# ECU_Sheet3.net
KiCad netlist of a schematic drawn in Altium Designer
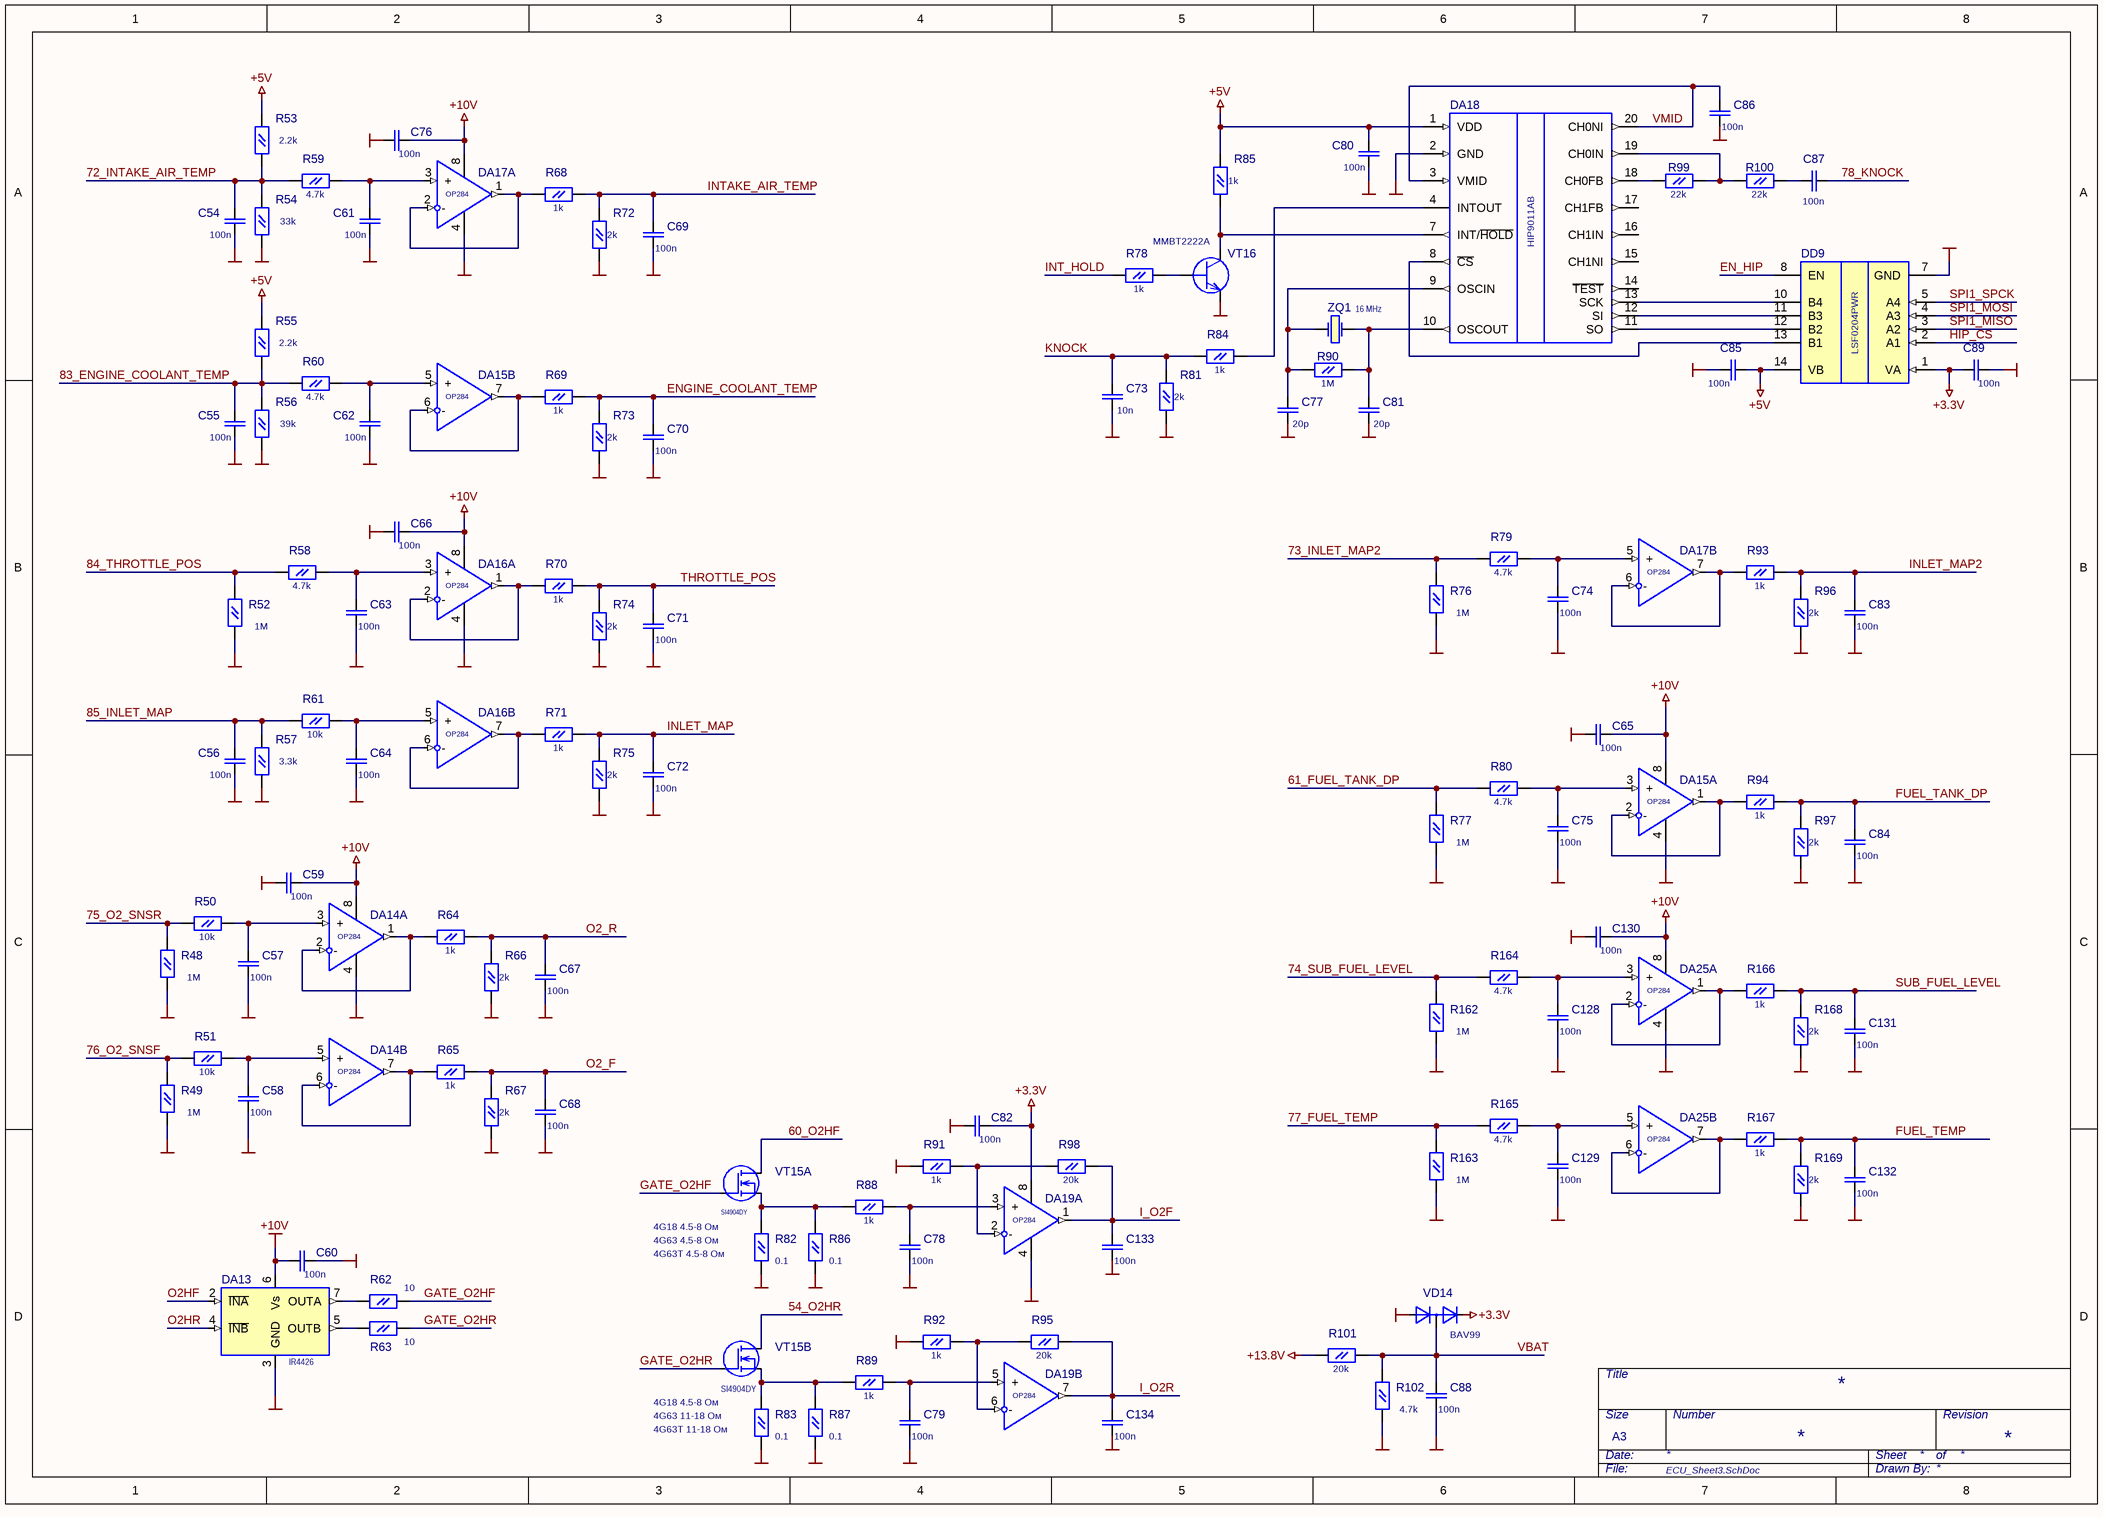
[diagram p0: ECU_Sheet3.SchDoc]

(export (version "E")
  (design (tool "Eeschema 10.0.6"))
  (components
    (comp (ref "C54")
      (value "100n")
      (footprint "C0805L")
      (description "C0603")
      (fields (field (name "Comment") "CSMD"))
      (libsource (lib "L1") (part "CSMD"))
    )
    (comp (ref "C55")
      (value "100n")
      (footprint "C0805L")
      (description "C0603")
      (fields (field (name "Comment") "CSMD"))
      (libsource (lib "L1") (part "CSMD"))
    )
    (comp (ref "C56")
      (value "100n")
      (footprint "C0805L")
      (description "C0603")
      (fields (field (name "Comment") "CSMD"))
      (libsource (lib "L1") (part "CSMD"))
    )
    (comp (ref "C57")
      (value "100n")
      (footprint "C0805L")
      (description "C0603")
      (fields (field (name "Comment") "CSMD"))
      (libsource (lib "L1") (part "CSMD"))
    )
    (comp (ref "C58")
      (value "100n")
      (footprint "C0805L")
      (description "C0603")
      (fields (field (name "Comment") "CSMD"))
      (libsource (lib "L1") (part "CSMD"))
    )
    (comp (ref "C59")
      (value "100n")
      (footprint "C0805L")
      (description "C0603")
      (fields (field (name "Comment") "CSMD"))
      (libsource (lib "L1") (part "CSMD"))
    )
    (comp (ref "C60")
      (value "100n")
      (footprint "C0805L")
      (description "C0603")
      (fields (field (name "Comment") "CSMD"))
      (libsource (lib "L1") (part "CSMD"))
    )
    (comp (ref "C61")
      (value "100n")
      (footprint "C0805L")
      (description "C0603")
      (fields (field (name "Comment") "CSMD"))
      (libsource (lib "L1") (part "CSMD"))
    )
    (comp (ref "C62")
      (value "100n")
      (footprint "C0805L")
      (description "C0603")
      (fields (field (name "Comment") "CSMD"))
      (libsource (lib "L1") (part "CSMD"))
    )
    (comp (ref "C63")
      (value "100n")
      (footprint "C0805L")
      (description "C0603")
      (fields (field (name "Comment") "CSMD"))
      (libsource (lib "L1") (part "CSMD"))
    )
    (comp (ref "C64")
      (value "100n")
      (footprint "C0805L")
      (description "C0603")
      (fields (field (name "Comment") "CSMD"))
      (libsource (lib "L1") (part "CSMD"))
    )
    (comp (ref "C65")
      (value "100n")
      (footprint "C0805L")
      (description "C0603")
      (fields (field (name "Comment") "CSMD"))
      (libsource (lib "L1") (part "CSMD"))
    )
    (comp (ref "C66")
      (value "100n")
      (footprint "C0805L")
      (description "C0603")
      (fields (field (name "Comment") "CSMD"))
      (libsource (lib "L1") (part "CSMD"))
    )
    (comp (ref "C67")
      (value "100n")
      (footprint "C0603L")
      (description "C0603")
      (fields (field (name "Comment") "CSMD"))
      (libsource (lib "L1") (part "CSMD"))
    )
    (comp (ref "C68")
      (value "100n")
      (footprint "C0603L")
      (description "C0603")
      (fields (field (name "Comment") "CSMD"))
      (libsource (lib "L1") (part "CSMD"))
    )
    (comp (ref "C69")
      (value "100n")
      (footprint "C0603L")
      (description "C0603")
      (fields (field (name "Comment") "CSMD"))
      (libsource (lib "L1") (part "CSMD"))
    )
    (comp (ref "C70")
      (value "100n")
      (footprint "C0603L")
      (description "C0603")
      (fields (field (name "Comment") "CSMD"))
      (libsource (lib "L1") (part "CSMD"))
    )
    (comp (ref "C71")
      (value "100n")
      (footprint "C0603L")
      (description "C0603")
      (fields (field (name "Comment") "CSMD"))
      (libsource (lib "L1") (part "CSMD"))
    )
    (comp (ref "C72")
      (value "100n")
      (footprint "C0603L")
      (description "C0603")
      (fields (field (name "Comment") "CSMD"))
      (libsource (lib "L1") (part "CSMD"))
    )
    (comp (ref "C73")
      (value "10n")
      (footprint "C0603L")
      (description "C0603")
      (fields (field (name "Comment") "CSMD"))
      (libsource (lib "L1") (part "CSMD"))
    )
    (comp (ref "C74")
      (value "100n")
      (footprint "C0805L")
      (description "C0603")
      (fields (field (name "Comment") "CSMD"))
      (libsource (lib "L1") (part "CSMD"))
    )
    (comp (ref "C75")
      (value "100n")
      (footprint "C0805L")
      (description "C0603")
      (fields (field (name "Comment") "CSMD"))
      (libsource (lib "L1") (part "CSMD"))
    )
    (comp (ref "C76")
      (value "100n")
      (footprint "C0805L")
      (description "C0603")
      (fields (field (name "Comment") "CSMD"))
      (libsource (lib "L1") (part "CSMD"))
    )
    (comp (ref "C77")
      (value "20p")
      (footprint "C0805L")
      (description "C0603")
      (fields (field (name "Comment") "CSMD"))
      (libsource (lib "L1") (part "CSMD"))
    )
    (comp (ref "C78")
      (value "100n")
      (footprint "C0805L")
      (description "C0603")
      (fields (field (name "Comment") "CSMD"))
      (libsource (lib "L1") (part "CSMD"))
    )
    (comp (ref "C79")
      (value "100n")
      (footprint "C0805L")
      (description "C0603")
      (fields (field (name "Comment") "CSMD"))
      (libsource (lib "L1") (part "CSMD"))
    )
    (comp (ref "C80")
      (value "100n")
      (footprint "C0805L")
      (description "C0603")
      (fields (field (name "Comment") "CSMD"))
      (libsource (lib "") (part "CSMD_1"))
    )
    (comp (ref "C81")
      (value "20p")
      (footprint "C0805L")
      (description "C0603")
      (fields (field (name "Comment") "CSMD"))
      (libsource (lib "L1") (part "CSMD"))
    )
    (comp (ref "C82")
      (value "100n")
      (footprint "C0805L")
      (description "C0603")
      (fields (field (name "Comment") "CSMD"))
      (libsource (lib "L1") (part "CSMD"))
    )
    (comp (ref "C83")
      (value "100n")
      (footprint "C0603L")
      (description "C0603")
      (fields (field (name "Comment") "CSMD"))
      (libsource (lib "L1") (part "CSMD"))
    )
    (comp (ref "C84")
      (value "100n")
      (footprint "C0603L")
      (description "C0603")
      (fields (field (name "Comment") "CSMD"))
      (libsource (lib "L1") (part "CSMD"))
    )
    (comp (ref "C85")
      (value "100n")
      (footprint "C0805L")
      (description "C0603")
      (fields (field (name "Comment") "CSMD"))
      (libsource (lib "L1") (part "CSMD"))
    )
    (comp (ref "C86")
      (value "100n")
      (footprint "C0805L")
      (description "C0603")
      (fields (field (name "Comment") "CSMD"))
      (libsource (lib "L1") (part "CSMD"))
    )
    (comp (ref "C87")
      (value "100n")
      (footprint "C0805L")
      (description "C0603")
      (fields (field (name "Comment") "CSMD"))
      (libsource (lib "L1") (part "CSMD"))
    )
    (comp (ref "C88")
      (value "100n")
      (footprint "C0603L")
      (description "C0603")
      (fields (field (name "Comment") "CSMD"))
      (libsource (lib "L1") (part "CSMD"))
    )
    (comp (ref "C89")
      (value "100n")
      (footprint "C0805L")
      (description "C0603")
      (fields (field (name "Comment") "CSMD"))
      (libsource (lib "L1") (part "CSMD"))
    )
    (comp (ref "C128")
      (value "100n")
      (footprint "C0805L")
      (description "C0603")
      (fields (field (name "Comment") "CSMD"))
      (libsource (lib "L1") (part "CSMD"))
    )
    (comp (ref "C129")
      (value "100n")
      (footprint "C0805L")
      (description "C0603")
      (fields (field (name "Comment") "CSMD"))
      (libsource (lib "L1") (part "CSMD"))
    )
    (comp (ref "C130")
      (value "100n")
      (footprint "C0805L")
      (description "C0603")
      (fields (field (name "Comment") "CSMD"))
      (libsource (lib "L1") (part "CSMD"))
    )
    (comp (ref "C131")
      (value "100n")
      (footprint "C0603L")
      (description "C0603")
      (fields (field (name "Comment") "CSMD"))
      (libsource (lib "L1") (part "CSMD"))
    )
    (comp (ref "C132")
      (value "100n")
      (footprint "C0603L")
      (description "C0603")
      (fields (field (name "Comment") "CSMD"))
      (libsource (lib "L1") (part "CSMD"))
    )
    (comp (ref "C133")
      (value "100n")
      (footprint "C0603L")
      (description "C0603")
      (fields (field (name "Comment") "CSMD"))
      (libsource (lib "L1") (part "CSMD"))
    )
    (comp (ref "C134")
      (value "100n")
      (footprint "C0603L")
      (description "C0603")
      (fields (field (name "Comment") "CSMD"))
      (libsource (lib "L1") (part "CSMD"))
    )
    (comp (ref "DA13") (value "IR4426") (footprint "SOIC8 JEDEC") (libsource (lib "SCH") (part "IR4426")))
    (comp (ref "DA14") (value "OP284") (footprint "SOIC8 JEDEC") (libsource (lib "RL1") (part "AD822")))
    (comp (ref "DA15") (value "OP284") (footprint "SOIC8 JEDEC") (libsource (lib "RL1") (part "AD822")))
    (comp (ref "DA16") (value "OP284") (footprint "SOIC8 JEDEC") (libsource (lib "RL1") (part "AD822")))
    (comp (ref "DA17") (value "OP284") (footprint "SOIC8 JEDEC") (libsource (lib "RL1") (part "AD822")))
    (comp (ref "DA18")
      (value "HIP9011AB")
      (footprint "SOIC-20 (JEDEC MS-013-AC)")
      (libsource (lib "ECULIB") (part "HIP9011AB"))
    )
    (comp (ref "DA19") (value "OP284") (footprint "SOIC8 JEDEC") (libsource (lib "RL1") (part "AD822")))
    (comp (ref "DA25") (value "OP284") (footprint "SOIC8 JEDEC") (libsource (lib "RL1") (part "AD822")))
    (comp (ref "DD9")
      (value "LSF0204PWR")
      (footprint "TSSOP14 (JEDEC MO-153)")
      (libsource (lib "L1") (part "LSF0204PWR"))
    )
    (comp (ref "R48")
      (value "1M")
      (footprint "R0805L")
      (description "R0805")
      (fields (field (name "Comment") "RSMD"))
      (libsource (lib "L1") (part "RSMD"))
    )
    (comp (ref "R49")
      (value "1M")
      (footprint "R0805L")
      (description "R0805")
      (fields (field (name "Comment") "RSMD"))
      (libsource (lib "L1") (part "RSMD"))
    )
    (comp (ref "R50")
      (value "10k")
      (footprint "R0805L")
      (description "R0805")
      (fields (field (name "Comment") "RSMD"))
      (libsource (lib "L1") (part "RSMD"))
    )
    (comp (ref "R51")
      (value "10k")
      (footprint "R0805L")
      (description "R0805")
      (fields (field (name "Comment") "RSMD"))
      (libsource (lib "L1") (part "RSMD"))
    )
    (comp (ref "R52")
      (value "1M")
      (footprint "R0805L")
      (description "R0805")
      (fields (field (name "Comment") "RSMD"))
      (libsource (lib "L1") (part "RSMD"))
    )
    (comp (ref "R53")
      (value "2.2k")
      (footprint "R0805L")
      (description "R0805")
      (fields (field (name "Comment") "RSMD"))
      (libsource (lib "L1") (part "RSMD"))
    )
    (comp (ref "R54")
      (value "33k")
      (footprint "R0805L")
      (description "R0805")
      (fields (field (name "Comment") "RSMD"))
      (libsource (lib "L1") (part "RSMD"))
    )
    (comp (ref "R55")
      (value "2.2k")
      (footprint "R0805L")
      (description "R0805")
      (fields (field (name "Comment") "RSMD"))
      (libsource (lib "L1") (part "RSMD"))
    )
    (comp (ref "R56")
      (value "39k")
      (footprint "R0805L")
      (description "R0805")
      (fields (field (name "Comment") "RSMD"))
      (libsource (lib "L1") (part "RSMD"))
    )
    (comp (ref "R57")
      (value "3.3k")
      (footprint "R0805L")
      (description "R0805")
      (fields (field (name "Comment") "RSMD"))
      (libsource (lib "L1") (part "RSMD"))
    )
    (comp (ref "R58")
      (value "4.7k")
      (footprint "R0805L")
      (description "R0805")
      (fields (field (name "Comment") "RSMD"))
      (libsource (lib "L1") (part "RSMD"))
    )
    (comp (ref "R59")
      (value "4.7k")
      (footprint "R0805L")
      (description "R0805")
      (fields (field (name "Comment") "RSMD"))
      (libsource (lib "L1") (part "RSMD"))
    )
    (comp (ref "R60")
      (value "4.7k")
      (footprint "R0805L")
      (description "R0805")
      (fields (field (name "Comment") "RSMD"))
      (libsource (lib "L1") (part "RSMD"))
    )
    (comp (ref "R61")
      (value "10k")
      (footprint "R0805L")
      (description "R0805")
      (fields (field (name "Comment") "RSMD"))
      (libsource (lib "L1") (part "RSMD"))
    )
    (comp (ref "R62")
      (value "10")
      (footprint "R0603L")
      (description "R0805")
      (fields (field (name "Comment") "RSMD"))
      (libsource (lib "L1") (part "RSMD"))
    )
    (comp (ref "R63")
      (value "10")
      (footprint "R0603L")
      (description "R0805")
      (fields (field (name "Comment") "RSMD"))
      (libsource (lib "L1") (part "RSMD"))
    )
    (comp (ref "R64")
      (value "1k")
      (footprint "R0805L")
      (description "R0805")
      (fields (field (name "Comment") "RSMD"))
      (libsource (lib "L1") (part "RSMD"))
    )
    (comp (ref "R65")
      (value "1k")
      (footprint "R0805L")
      (description "R0805")
      (fields (field (name "Comment") "RSMD"))
      (libsource (lib "L1") (part "RSMD"))
    )
    (comp (ref "R66")
      (value "2k")
      (footprint "R0805L")
      (description "R0805")
      (fields (field (name "Comment") "RSMD"))
      (libsource (lib "L1") (part "RSMD"))
    )
    (comp (ref "R67")
      (value "2k")
      (footprint "R0805L")
      (description "R0805")
      (fields (field (name "Comment") "RSMD"))
      (libsource (lib "L1") (part "RSMD"))
    )
    (comp (ref "R68")
      (value "1k")
      (footprint "R0805L")
      (description "R0805")
      (fields (field (name "Comment") "RSMD"))
      (libsource (lib "L1") (part "RSMD"))
    )
    (comp (ref "R69")
      (value "1k")
      (footprint "R0805L")
      (description "R0805")
      (fields (field (name "Comment") "RSMD"))
      (libsource (lib "L1") (part "RSMD"))
    )
    (comp (ref "R70")
      (value "1k")
      (footprint "R0805L")
      (description "R0805")
      (fields (field (name "Comment") "RSMD"))
      (libsource (lib "L1") (part "RSMD"))
    )
    (comp (ref "R71")
      (value "1k")
      (footprint "R0805L")
      (description "R0805")
      (fields (field (name "Comment") "RSMD"))
      (libsource (lib "L1") (part "RSMD"))
    )
    (comp (ref "R72")
      (value "2k")
      (footprint "R0805L")
      (description "R0805")
      (fields (field (name "Comment") "RSMD"))
      (libsource (lib "L1") (part "RSMD"))
    )
    (comp (ref "R73")
      (value "2k")
      (footprint "R0805L")
      (description "R0805")
      (fields (field (name "Comment") "RSMD"))
      (libsource (lib "L1") (part "RSMD"))
    )
    (comp (ref "R74")
      (value "2k")
      (footprint "R0805L")
      (description "R0805")
      (fields (field (name "Comment") "RSMD"))
      (libsource (lib "L1") (part "RSMD"))
    )
    (comp (ref "R75")
      (value "2k")
      (footprint "R0805L")
      (description "R0805")
      (fields (field (name "Comment") "RSMD"))
      (libsource (lib "L1") (part "RSMD"))
    )
    (comp (ref "R76")
      (value "1M")
      (footprint "R0805L")
      (description "R0805")
      (fields (field (name "Comment") "RSMD"))
      (libsource (lib "L1") (part "RSMD"))
    )
    (comp (ref "R77")
      (value "1M")
      (footprint "R0805L")
      (description "R0805")
      (fields (field (name "Comment") "RSMD"))
      (libsource (lib "L1") (part "RSMD"))
    )
    (comp (ref "R78")
      (value "1k")
      (footprint "R0805L")
      (description "R0805")
      (fields (field (name "Comment") "RSMD"))
      (libsource (lib "L1") (part "RSMD"))
    )
    (comp (ref "R79")
      (value "4.7k")
      (footprint "R0805L")
      (description "R0805")
      (fields (field (name "Comment") "RSMD"))
      (libsource (lib "L1") (part "RSMD"))
    )
    (comp (ref "R80")
      (value "4.7k")
      (footprint "R0805L")
      (description "R0805")
      (fields (field (name "Comment") "RSMD"))
      (libsource (lib "L1") (part "RSMD"))
    )
    (comp (ref "R81")
      (value "2k")
      (footprint "R0805L")
      (description "R0805")
      (fields (field (name "Comment") "RSMD"))
      (libsource (lib "L1") (part "RSMD"))
    )
    (comp (ref "R82")
      (value "0.1")
      (footprint "R0805L")
      (description "R0805")
      (fields (field (name "Comment") "RSMD"))
      (libsource (lib "L1") (part "RSMD"))
    )
    (comp (ref "R83")
      (value "0.1")
      (footprint "R0805L")
      (description "R0805")
      (fields (field (name "Comment") "RSMD"))
      (libsource (lib "L1") (part "RSMD"))
    )
    (comp (ref "R84")
      (value "1k")
      (footprint "R0805L")
      (description "R0805")
      (fields (field (name "Comment") "RSMD"))
      (libsource (lib "L1") (part "RSMD"))
    )
    (comp (ref "R85")
      (value "1k")
      (footprint "R0805L")
      (description "R0805")
      (fields (field (name "Comment") "RSMD"))
      (libsource (lib "L1") (part "RSMD"))
    )
    (comp (ref "R86")
      (value "0.1")
      (footprint "R0805L")
      (description "R0805")
      (fields (field (name "Comment") "RSMD"))
      (libsource (lib "L1") (part "RSMD"))
    )
    (comp (ref "R87")
      (value "0.1")
      (footprint "R0805L")
      (description "R0805")
      (fields (field (name "Comment") "RSMD"))
      (libsource (lib "L1") (part "RSMD"))
    )
    (comp (ref "R88")
      (value "1k")
      (footprint "R0805L")
      (description "R0805")
      (fields (field (name "Comment") "RSMD"))
      (libsource (lib "L1") (part "RSMD"))
    )
    (comp (ref "R89")
      (value "1k")
      (footprint "R0805L")
      (description "R0805")
      (fields (field (name "Comment") "RSMD"))
      (libsource (lib "L1") (part "RSMD"))
    )
    (comp (ref "R90")
      (value "1M")
      (footprint "R0805L")
      (description "R0805")
      (fields (field (name "Comment") "RSMD"))
      (libsource (lib "L1") (part "RSMD"))
    )
    (comp (ref "R91")
      (value "1k")
      (footprint "R0805L")
      (description "R0805")
      (fields (field (name "Comment") "RSMD"))
      (libsource (lib "L1") (part "RSMD"))
    )
    (comp (ref "R92")
      (value "1k")
      (footprint "R0805L")
      (description "R0805")
      (fields (field (name "Comment") "RSMD"))
      (libsource (lib "L1") (part "RSMD"))
    )
    (comp (ref "R93")
      (value "1k")
      (footprint "R0805L")
      (description "R0805")
      (fields (field (name "Comment") "RSMD"))
      (libsource (lib "L1") (part "RSMD"))
    )
    (comp (ref "R94")
      (value "1k")
      (footprint "R0805L")
      (description "R0805")
      (fields (field (name "Comment") "RSMD"))
      (libsource (lib "L1") (part "RSMD"))
    )
    (comp (ref "R95")
      (value "20k")
      (footprint "R0805L")
      (description "R0805")
      (fields (field (name "Comment") "RSMD"))
      (libsource (lib "L1") (part "RSMD"))
    )
    (comp (ref "R96")
      (value "2k")
      (footprint "R0805L")
      (description "R0805")
      (fields (field (name "Comment") "RSMD"))
      (libsource (lib "L1") (part "RSMD"))
    )
    (comp (ref "R97")
      (value "2k")
      (footprint "R0805L")
      (description "R0805")
      (fields (field (name "Comment") "RSMD"))
      (libsource (lib "L1") (part "RSMD"))
    )
    (comp (ref "R98")
      (value "20k")
      (footprint "R0805L")
      (description "R0805")
      (fields (field (name "Comment") "RSMD"))
      (libsource (lib "L1") (part "RSMD"))
    )
    (comp (ref "R99")
      (value "22k")
      (footprint "R0805L")
      (description "R0805")
      (fields (field (name "Comment") "RSMD"))
      (libsource (lib "L1") (part "RSMD"))
    )
    (comp (ref "R100")
      (value "22k")
      (footprint "R0805L")
      (description "R0805")
      (fields (field (name "Comment") "RSMD"))
      (libsource (lib "L1") (part "RSMD"))
    )
    (comp (ref "R101")
      (value "20k")
      (footprint "R0805L")
      (description "R0805")
      (fields (field (name "Comment") "RSMD"))
      (libsource (lib "L1") (part "RSMD"))
    )
    (comp (ref "R102")
      (value "4.7k")
      (footprint "R0805L")
      (description "R0805")
      (fields (field (name "Comment") "RSMD"))
      (libsource (lib "L1") (part "RSMD"))
    )
    (comp (ref "R162")
      (value "1M")
      (footprint "R0805L")
      (description "R0805")
      (fields (field (name "Comment") "RSMD"))
      (libsource (lib "L1") (part "RSMD"))
    )
    (comp (ref "R163")
      (value "1M")
      (footprint "R0805L")
      (description "R0805")
      (fields (field (name "Comment") "RSMD"))
      (libsource (lib "L1") (part "RSMD"))
    )
    (comp (ref "R164")
      (value "4.7k")
      (footprint "R0805L")
      (description "R0805")
      (fields (field (name "Comment") "RSMD"))
      (libsource (lib "L1") (part "RSMD"))
    )
    (comp (ref "R165")
      (value "4.7k")
      (footprint "R0805L")
      (description "R0805")
      (fields (field (name "Comment") "RSMD"))
      (libsource (lib "L1") (part "RSMD"))
    )
    (comp (ref "R166")
      (value "1k")
      (footprint "R0805L")
      (description "R0805")
      (fields (field (name "Comment") "RSMD"))
      (libsource (lib "L1") (part "RSMD"))
    )
    (comp (ref "R167")
      (value "1k")
      (footprint "R0805L")
      (description "R0805")
      (fields (field (name "Comment") "RSMD"))
      (libsource (lib "L1") (part "RSMD"))
    )
    (comp (ref "R168")
      (value "2k")
      (footprint "R0805L")
      (description "R0805")
      (fields (field (name "Comment") "RSMD"))
      (libsource (lib "L1") (part "RSMD"))
    )
    (comp (ref "R169")
      (value "2k")
      (footprint "R0805L")
      (description "R0805")
      (fields (field (name "Comment") "RSMD"))
      (libsource (lib "L1") (part "RSMD"))
    )
    (comp (ref "VD14") (value "BAV99") (footprint "SOT-23") (libsource (lib "RL1") (part "BAV99")))
    (comp (ref "VT15")
      (value "SI4904DY")
      (footprint "SOIC8 DBL FET")
      (description "SI4904DY или IRF7341TRPBF или SI4908DY")
      (libsource (lib "L1") (part "SQ9945BEY"))
    )
    (comp (ref "VT16")
      (value "MMBT2222A")
      (footprint "SOT-23_MMBT2222A(Primary)")
      (libsource (lib "RL1") (part "MMBT2222A"))
    )
    (comp (ref "ZQ1")
      (value "16 MHz")
      (footprint "HC-49/S")
      (description "KX-3НЕ-16.0 MHz")
      (libsource (lib "*") (part "QUARZ"))
    )
  )
  (nets
    (net (code "1") (name "+3.3V") (class "Default")
      (node (ref "C82") (pin "1") (pintype "passive"))
      (node (ref "C89") (pin "2") (pintype "passive"))
      (node (ref "DA19") (pin "8") (pinfunction "V+_8") (pintype "power_in"))
      (node (ref "DD9") (pin "1") (pinfunction "VA_1") (pintype "input"))
      (node (ref "VD14") (pin "2") (pinfunction "K_2") (pintype "passive"))
    )
    (net (code "2") (name "+5V") (class "Default")
      (node (ref "C80") (pin "2") (pintype "passive"))
      (node (ref "C85") (pin "2") (pintype "passive"))
      (node (ref "DA18") (pin "1") (pinfunction "VDD_1") (pintype "input"))
      (node (ref "DD9") (pin "14") (pinfunction "VB_14") (pintype "power_in"))
      (node (ref "R53") (pin "2") (pinfunction "Pin2_2") (pintype "passive"))
      (node (ref "R55") (pin "2") (pinfunction "Pin2_2") (pintype "passive"))
      (node (ref "R85") (pin "2") (pinfunction "Pin2_2") (pintype "passive"))
    )
    (net (code "3") (name "+10V") (class "Default")
      (node (ref "C130") (pin "1") (pintype "passive"))
      (node (ref "C59") (pin "1") (pintype "passive"))
      (node (ref "C60") (pin "2") (pintype "passive"))
      (node (ref "C65") (pin "1") (pintype "passive"))
      (node (ref "C66") (pin "1") (pintype "passive"))
      (node (ref "C76") (pin "1") (pintype "passive"))
      (node (ref "DA13") (pin "6") (pinfunction "Vs_6") (pintype "power_in"))
      (node (ref "DA14") (pin "8") (pinfunction "V+_8") (pintype "power_in"))
      (node (ref "DA15") (pin "8") (pinfunction "V+_8") (pintype "power_in"))
      (node (ref "DA16") (pin "8") (pinfunction "V+_8") (pintype "power_in"))
      (node (ref "DA17") (pin "8") (pinfunction "V+_8") (pintype "power_in"))
      (node (ref "DA25") (pin "8") (pinfunction "V+_8") (pintype "power_in"))
    )
    (net (code "4") (name "+13.8V") (class "Default")
      (node (ref "R101") (pin "1") (pinfunction "Pin1_1") (pintype "passive"))
    )
    (net (code "5") (name "/54_O2HR") (class "Default") (node (ref "VT15") (pin "5") (pintype "passive")))
    (net (code "6") (name "/60_O2HF") (class "Default") (node (ref "VT15") (pin "6") (pintype "passive")))
    (net (code "7") (name "/61_FUEL_TANK_DP") (class "Default")
      (node (ref "R77") (pin "2") (pinfunction "Pin2_2") (pintype "passive"))
      (node (ref "R80") (pin "1") (pinfunction "Pin1_1") (pintype "passive"))
    )
    (net (code "8") (name "/72_INTAKE_AIR_TEMP") (class "Default")
      (node (ref "C54") (pin "1") (pintype "passive"))
      (node (ref "R53") (pin "1") (pinfunction "Pin1_1") (pintype "passive"))
      (node (ref "R54") (pin "2") (pinfunction "Pin2_2") (pintype "passive"))
      (node (ref "R59") (pin "1") (pinfunction "Pin1_1") (pintype "passive"))
    )
    (net (code "9") (name "/73_INLET_MAP2") (class "Default")
      (node (ref "R76") (pin "2") (pinfunction "Pin2_2") (pintype "passive"))
      (node (ref "R79") (pin "1") (pinfunction "Pin1_1") (pintype "passive"))
    )
    (net (code "10") (name "/74_SUB_FUEL_LEVEL") (class "Default")
      (node (ref "R162") (pin "2") (pinfunction "Pin2_2") (pintype "passive"))
      (node (ref "R164") (pin "1") (pinfunction "Pin1_1") (pintype "passive"))
    )
    (net (code "11") (name "/75_O2_SNSR") (class "Default")
      (node (ref "R48") (pin "2") (pinfunction "Pin2_2") (pintype "passive"))
      (node (ref "R50") (pin "1") (pinfunction "Pin1_1") (pintype "passive"))
    )
    (net (code "12") (name "/76_O2_SNSF") (class "Default")
      (node (ref "R49") (pin "2") (pinfunction "Pin2_2") (pintype "passive"))
      (node (ref "R51") (pin "1") (pinfunction "Pin1_1") (pintype "passive"))
    )
    (net (code "13") (name "/77_FUEL_TEMP") (class "Default")
      (node (ref "R163") (pin "2") (pinfunction "Pin2_2") (pintype "passive"))
      (node (ref "R165") (pin "1") (pinfunction "Pin1_1") (pintype "passive"))
    )
    (net (code "14") (name "/78_KNOCK") (class "Default") (node (ref "C87") (pin "2") (pintype "passive")))
    (net (code "15") (name "/83_ENGINE_COOLANT_TEMP") (class "Default")
      (node (ref "C55") (pin "1") (pintype "passive"))
      (node (ref "R55") (pin "1") (pinfunction "Pin1_1") (pintype "passive"))
      (node (ref "R56") (pin "2") (pinfunction "Pin2_2") (pintype "passive"))
      (node (ref "R60") (pin "1") (pinfunction "Pin1_1") (pintype "passive"))
    )
    (net (code "16") (name "/84_THROTTLE_POS") (class "Default")
      (node (ref "R52") (pin "2") (pinfunction "Pin2_2") (pintype "passive"))
      (node (ref "R58") (pin "1") (pinfunction "Pin1_1") (pintype "passive"))
    )
    (net (code "17") (name "/85_INLET_MAP") (class "Default")
      (node (ref "C56") (pin "1") (pintype "passive"))
      (node (ref "R57") (pin "2") (pinfunction "Pin2_2") (pintype "passive"))
      (node (ref "R61") (pin "1") (pinfunction "Pin1_1") (pintype "passive"))
    )
    (net (code "18") (name "/ENGINE_COOLANT_TEMP") (class "Default")
      (node (ref "C70") (pin "1") (pintype "passive"))
      (node (ref "R69") (pin "2") (pinfunction "Pin2_2") (pintype "passive"))
      (node (ref "R73") (pin "2") (pinfunction "Pin2_2") (pintype "passive"))
    )
    (net (code "19") (name "/EN_HIP") (class "Default")
      (node (ref "DD9") (pin "8") (pinfunction "EN_8") (pintype "power_in"))
    )
    (net (code "20") (name "/FUEL_TANK_DP") (class "Default")
      (node (ref "C84") (pin "1") (pintype "passive"))
      (node (ref "R94") (pin "2") (pinfunction "Pin2_2") (pintype "passive"))
      (node (ref "R97") (pin "2") (pinfunction "Pin2_2") (pintype "passive"))
    )
    (net (code "21") (name "/FUEL_TEMP") (class "Default")
      (node (ref "C132") (pin "1") (pintype "passive"))
      (node (ref "R167") (pin "2") (pinfunction "Pin2_2") (pintype "passive"))
      (node (ref "R169") (pin "2") (pinfunction "Pin2_2") (pintype "passive"))
    )
    (net (code "22") (name "/GATE_O2HF") (class "Default")
      (node (ref "R62") (pin "2") (pinfunction "Pin2_2") (pintype "passive"))
      (node (ref "VT15") (pin "2") (pintype "passive"))
    )
    (net (code "23") (name "/GATE_O2HR") (class "Default")
      (node (ref "R63") (pin "2") (pinfunction "Pin2_2") (pintype "passive"))
      (node (ref "VT15") (pin "4") (pintype "passive"))
    )
    (net (code "24") (name "/HIP_CS") (class "Default")
      (node (ref "DD9") (pin "2") (pinfunction "A1_2") (pintype "input"))
    )
    (net (code "25") (name "/INLET_MAP") (class "Default")
      (node (ref "C72") (pin "1") (pintype "passive"))
      (node (ref "R71") (pin "2") (pinfunction "Pin2_2") (pintype "passive"))
      (node (ref "R75") (pin "2") (pinfunction "Pin2_2") (pintype "passive"))
    )
    (net (code "26") (name "/INLET_MAP2") (class "Default")
      (node (ref "C83") (pin "1") (pintype "passive"))
      (node (ref "R93") (pin "2") (pinfunction "Pin2_2") (pintype "passive"))
      (node (ref "R96") (pin "2") (pinfunction "Pin2_2") (pintype "passive"))
    )
    (net (code "27") (name "/INTAKE_AIR_TEMP") (class "Default")
      (node (ref "C69") (pin "1") (pintype "passive"))
      (node (ref "R68") (pin "2") (pinfunction "Pin2_2") (pintype "passive"))
      (node (ref "R72") (pin "2") (pinfunction "Pin2_2") (pintype "passive"))
    )
    (net (code "28") (name "/INT_HOLD") (class "Default")
      (node (ref "R78") (pin "1") (pinfunction "Pin1_1") (pintype "passive"))
    )
    (net (code "29") (name "/I_O2F") (class "Default")
      (node (ref "C133") (pin "1") (pintype "passive"))
      (node (ref "DA19") (pin "1") (pinfunction "OUT_1") (pintype "output"))
      (node (ref "R98") (pin "2") (pinfunction "Pin2_2") (pintype "passive"))
    )
    (net (code "30") (name "/I_O2R") (class "Default")
      (node (ref "C134") (pin "1") (pintype "passive"))
      (node (ref "DA19") (pin "7") (pinfunction "OUT_7") (pintype "output"))
      (node (ref "R95") (pin "2") (pinfunction "Pin2_2") (pintype "passive"))
    )
    (net (code "31") (name "/KNOCK") (class "Default")
      (node (ref "C73") (pin "1") (pintype "passive"))
      (node (ref "R81") (pin "2") (pinfunction "Pin2_2") (pintype "passive"))
      (node (ref "R84") (pin "1") (pinfunction "Pin1_1") (pintype "passive"))
    )
    (net (code "32") (name "/O2HF") (class "Default")
      (node (ref "DA13") (pin "2") (pinfunction "~{INA}_2") (pintype "input"))
    )
    (net (code "33") (name "/O2HR") (class "Default")
      (node (ref "DA13") (pin "4") (pinfunction "~{INB}_4") (pintype "input"))
    )
    (net (code "34") (name "/O2_F") (class "Default")
      (node (ref "C68") (pin "1") (pintype "passive"))
      (node (ref "R65") (pin "2") (pinfunction "Pin2_2") (pintype "passive"))
      (node (ref "R67") (pin "2") (pinfunction "Pin2_2") (pintype "passive"))
    )
    (net (code "35") (name "/O2_R") (class "Default")
      (node (ref "C67") (pin "1") (pintype "passive"))
      (node (ref "R64") (pin "2") (pinfunction "Pin2_2") (pintype "passive"))
      (node (ref "R66") (pin "2") (pinfunction "Pin2_2") (pintype "passive"))
    )
    (net (code "36") (name "/SPI1_MISO") (class "Default")
      (node (ref "DD9") (pin "3") (pinfunction "A2_3") (pintype "input"))
    )
    (net (code "37") (name "/SPI1_MOSI") (class "Default")
      (node (ref "DD9") (pin "4") (pinfunction "A3_4") (pintype "input"))
    )
    (net (code "38") (name "/SPI1_SPCK") (class "Default")
      (node (ref "DD9") (pin "5") (pinfunction "A4_5") (pintype "input"))
    )
    (net (code "39") (name "/SUB_FUEL_LEVEL") (class "Default")
      (node (ref "C131") (pin "1") (pintype "passive"))
      (node (ref "R166") (pin "2") (pinfunction "Pin2_2") (pintype "passive"))
      (node (ref "R168") (pin "2") (pinfunction "Pin2_2") (pintype "passive"))
    )
    (net (code "40") (name "/THROTTLE_POS") (class "Default")
      (node (ref "C71") (pin "1") (pintype "passive"))
      (node (ref "R70") (pin "2") (pinfunction "Pin2_2") (pintype "passive"))
      (node (ref "R74") (pin "2") (pinfunction "Pin2_2") (pintype "passive"))
    )
    (net (code "41") (name "/VBAT") (class "Default")
      (node (ref "C88") (pin "1") (pintype "passive"))
      (node (ref "R101") (pin "2") (pinfunction "Pin2_2") (pintype "passive"))
      (node (ref "R102") (pin "2") (pinfunction "Pin2_2") (pintype "passive"))
      (node (ref "VD14") (pin "3") (pinfunction "C_3") (pintype "passive"))
    )
    (net (code "42") (name "/VMID") (class "Default")
      (node (ref "C86") (pin "1") (pintype "passive"))
      (node (ref "DA18") (pin "20") (pinfunction "CH0NI_20") (pintype "output"))
      (node (ref "DA18") (pin "3") (pinfunction "VMID_3") (pintype "input"))
    )
    (net (code "43") (name "GND") (class "Default")
      (node (ref "C128") (pin "2") (pintype "passive"))
      (node (ref "C129") (pin "2") (pintype "passive"))
      (node (ref "C130") (pin "2") (pintype "passive"))
      (node (ref "C131") (pin "2") (pintype "passive"))
      (node (ref "C132") (pin "2") (pintype "passive"))
      (node (ref "C133") (pin "2") (pintype "passive"))
      (node (ref "C134") (pin "2") (pintype "passive"))
      (node (ref "C54") (pin "2") (pintype "passive"))
      (node (ref "C55") (pin "2") (pintype "passive"))
      (node (ref "C56") (pin "2") (pintype "passive"))
      (node (ref "C57") (pin "2") (pintype "passive"))
      (node (ref "C58") (pin "2") (pintype "passive"))
      (node (ref "C59") (pin "2") (pintype "passive"))
      (node (ref "C60") (pin "1") (pintype "passive"))
      (node (ref "C61") (pin "2") (pintype "passive"))
      (node (ref "C62") (pin "2") (pintype "passive"))
      (node (ref "C63") (pin "2") (pintype "passive"))
      (node (ref "C64") (pin "2") (pintype "passive"))
      (node (ref "C65") (pin "2") (pintype "passive"))
      (node (ref "C66") (pin "2") (pintype "passive"))
      (node (ref "C67") (pin "2") (pintype "passive"))
      (node (ref "C68") (pin "2") (pintype "passive"))
      (node (ref "C69") (pin "2") (pintype "passive"))
      (node (ref "C70") (pin "2") (pintype "passive"))
      (node (ref "C71") (pin "2") (pintype "passive"))
      (node (ref "C72") (pin "2") (pintype "passive"))
      (node (ref "C73") (pin "2") (pintype "passive"))
      (node (ref "C74") (pin "2") (pintype "passive"))
      (node (ref "C75") (pin "2") (pintype "passive"))
      (node (ref "C76") (pin "2") (pintype "passive"))
      (node (ref "C77") (pin "2") (pintype "passive"))
      (node (ref "C78") (pin "2") (pintype "passive"))
      (node (ref "C79") (pin "2") (pintype "passive"))
      (node (ref "C80") (pin "1") (pintype "passive"))
      (node (ref "C81") (pin "2") (pintype "passive"))
      (node (ref "C82") (pin "2") (pintype "passive"))
      (node (ref "C83") (pin "2") (pintype "passive"))
      (node (ref "C84") (pin "2") (pintype "passive"))
      (node (ref "C85") (pin "1") (pintype "passive"))
      (node (ref "C86") (pin "2") (pintype "passive"))
      (node (ref "C88") (pin "2") (pintype "passive"))
      (node (ref "C89") (pin "1") (pintype "passive"))
      (node (ref "DA13") (pin "3") (pinfunction "GND_3") (pintype "power_in"))
      (node (ref "DA14") (pin "4") (pinfunction "V-_4") (pintype "power_in"))
      (node (ref "DA15") (pin "4") (pinfunction "V-_4") (pintype "power_in"))
      (node (ref "DA16") (pin "4") (pinfunction "V-_4") (pintype "power_in"))
      (node (ref "DA17") (pin "4") (pinfunction "V-_4") (pintype "power_in"))
      (node (ref "DA18") (pin "2") (pinfunction "GND_2") (pintype "input"))
      (node (ref "DA19") (pin "4") (pinfunction "V-_4") (pintype "power_in"))
      (node (ref "DA25") (pin "4") (pinfunction "V-_4") (pintype "power_in"))
      (node (ref "DD9") (pin "7") (pinfunction "GND_7") (pintype "power_in"))
      (node (ref "R102") (pin "1") (pinfunction "Pin1_1") (pintype "passive"))
      (node (ref "R162") (pin "1") (pinfunction "Pin1_1") (pintype "passive"))
      (node (ref "R163") (pin "1") (pinfunction "Pin1_1") (pintype "passive"))
      (node (ref "R168") (pin "1") (pinfunction "Pin1_1") (pintype "passive"))
      (node (ref "R169") (pin "1") (pinfunction "Pin1_1") (pintype "passive"))
      (node (ref "R48") (pin "1") (pinfunction "Pin1_1") (pintype "passive"))
      (node (ref "R49") (pin "1") (pinfunction "Pin1_1") (pintype "passive"))
      (node (ref "R52") (pin "1") (pinfunction "Pin1_1") (pintype "passive"))
      (node (ref "R54") (pin "1") (pinfunction "Pin1_1") (pintype "passive"))
      (node (ref "R56") (pin "1") (pinfunction "Pin1_1") (pintype "passive"))
      (node (ref "R57") (pin "1") (pinfunction "Pin1_1") (pintype "passive"))
      (node (ref "R66") (pin "1") (pinfunction "Pin1_1") (pintype "passive"))
      (node (ref "R67") (pin "1") (pinfunction "Pin1_1") (pintype "passive"))
      (node (ref "R72") (pin "1") (pinfunction "Pin1_1") (pintype "passive"))
      (node (ref "R73") (pin "1") (pinfunction "Pin1_1") (pintype "passive"))
      (node (ref "R74") (pin "1") (pinfunction "Pin1_1") (pintype "passive"))
      (node (ref "R75") (pin "1") (pinfunction "Pin1_1") (pintype "passive"))
      (node (ref "R76") (pin "1") (pinfunction "Pin1_1") (pintype "passive"))
      (node (ref "R77") (pin "1") (pinfunction "Pin1_1") (pintype "passive"))
      (node (ref "R81") (pin "1") (pinfunction "Pin1_1") (pintype "passive"))
      (node (ref "R82") (pin "2") (pinfunction "Pin2_2") (pintype "passive"))
      (node (ref "R83") (pin "2") (pinfunction "Pin2_2") (pintype "passive"))
      (node (ref "R86") (pin "2") (pinfunction "Pin2_2") (pintype "passive"))
      (node (ref "R87") (pin "2") (pinfunction "Pin2_2") (pintype "passive"))
      (node (ref "R91") (pin "1") (pinfunction "Pin1_1") (pintype "passive"))
      (node (ref "R92") (pin "1") (pinfunction "Pin1_1") (pintype "passive"))
      (node (ref "R96") (pin "1") (pinfunction "Pin1_1") (pintype "passive"))
      (node (ref "R97") (pin "1") (pinfunction "Pin1_1") (pintype "passive"))
      (node (ref "VD14") (pin "1") (pinfunction "A_1") (pintype "passive"))
      (node (ref "VT16") (pin "3") (pinfunction "E_3") (pintype "passive"))
    )
    (net (code "44") (name "Net-(DA13-OUTA)") (class "Default")
      (node (ref "DA13") (pin "7") (pinfunction "OUTA_7") (pintype "output"))
      (node (ref "R62") (pin "1") (pinfunction "Pin1_1") (pintype "passive"))
    )
    (net (code "45") (name "Net-(DA13-OUTB)") (class "Default")
      (node (ref "DA13") (pin "5") (pinfunction "OUTB_5") (pintype "output"))
      (node (ref "R63") (pin "1") (pinfunction "Pin1_1") (pintype "passive"))
    )
    (net (code "46") (name "Net-(DA14A-+)") (class "Default")
      (node (ref "C57") (pin "1") (pintype "passive"))
      (node (ref "DA14") (pin "3") (pinfunction "+_3") (pintype "input"))
      (node (ref "R50") (pin "2") (pinfunction "Pin2_2") (pintype "passive"))
    )
    (net (code "47") (name "Net-(DA14A--)") (class "Default")
      (node (ref "DA14") (pin "1") (pinfunction "OUT_1") (pintype "output"))
      (node (ref "DA14") (pin "2") (pinfunction "-_2") (pintype "input"))
      (node (ref "R64") (pin "1") (pinfunction "Pin1_1") (pintype "passive"))
    )
    (net (code "48") (name "Net-(DA14B-+)") (class "Default")
      (node (ref "C58") (pin "1") (pintype "passive"))
      (node (ref "DA14") (pin "5") (pinfunction "+_5") (pintype "input"))
      (node (ref "R51") (pin "2") (pinfunction "Pin2_2") (pintype "passive"))
    )
    (net (code "49") (name "Net-(DA14B--)") (class "Default")
      (node (ref "DA14") (pin "6") (pinfunction "-_6") (pintype "input"))
      (node (ref "DA14") (pin "7") (pinfunction "OUT_7") (pintype "output"))
      (node (ref "R65") (pin "1") (pinfunction "Pin1_1") (pintype "passive"))
    )
    (net (code "50") (name "Net-(DA15A-+)") (class "Default")
      (node (ref "C75") (pin "1") (pintype "passive"))
      (node (ref "DA15") (pin "3") (pinfunction "+_3") (pintype "input"))
      (node (ref "R80") (pin "2") (pinfunction "Pin2_2") (pintype "passive"))
    )
    (net (code "51") (name "Net-(DA15A--)") (class "Default")
      (node (ref "DA15") (pin "1") (pinfunction "OUT_1") (pintype "output"))
      (node (ref "DA15") (pin "2") (pinfunction "-_2") (pintype "input"))
      (node (ref "R94") (pin "1") (pinfunction "Pin1_1") (pintype "passive"))
    )
    (net (code "52") (name "Net-(DA15B-+)") (class "Default")
      (node (ref "C62") (pin "1") (pintype "passive"))
      (node (ref "DA15") (pin "5") (pinfunction "+_5") (pintype "input"))
      (node (ref "R60") (pin "2") (pinfunction "Pin2_2") (pintype "passive"))
    )
    (net (code "53") (name "Net-(DA15B--)") (class "Default")
      (node (ref "DA15") (pin "6") (pinfunction "-_6") (pintype "input"))
      (node (ref "DA15") (pin "7") (pinfunction "OUT_7") (pintype "output"))
      (node (ref "R69") (pin "1") (pinfunction "Pin1_1") (pintype "passive"))
    )
    (net (code "54") (name "Net-(DA16A-+)") (class "Default")
      (node (ref "C63") (pin "1") (pintype "passive"))
      (node (ref "DA16") (pin "3") (pinfunction "+_3") (pintype "input"))
      (node (ref "R58") (pin "2") (pinfunction "Pin2_2") (pintype "passive"))
    )
    (net (code "55") (name "Net-(DA16A--)") (class "Default")
      (node (ref "DA16") (pin "1") (pinfunction "OUT_1") (pintype "output"))
      (node (ref "DA16") (pin "2") (pinfunction "-_2") (pintype "input"))
      (node (ref "R70") (pin "1") (pinfunction "Pin1_1") (pintype "passive"))
    )
    (net (code "56") (name "Net-(DA16B-+)") (class "Default")
      (node (ref "C64") (pin "1") (pintype "passive"))
      (node (ref "DA16") (pin "5") (pinfunction "+_5") (pintype "input"))
      (node (ref "R61") (pin "2") (pinfunction "Pin2_2") (pintype "passive"))
    )
    (net (code "57") (name "Net-(DA16B--)") (class "Default")
      (node (ref "DA16") (pin "6") (pinfunction "-_6") (pintype "input"))
      (node (ref "DA16") (pin "7") (pinfunction "OUT_7") (pintype "output"))
      (node (ref "R71") (pin "1") (pinfunction "Pin1_1") (pintype "passive"))
    )
    (net (code "58") (name "Net-(DA17A-+)") (class "Default")
      (node (ref "C61") (pin "1") (pintype "passive"))
      (node (ref "DA17") (pin "3") (pinfunction "+_3") (pintype "input"))
      (node (ref "R59") (pin "2") (pinfunction "Pin2_2") (pintype "passive"))
    )
    (net (code "59") (name "Net-(DA17A--)") (class "Default")
      (node (ref "DA17") (pin "1") (pinfunction "OUT_1") (pintype "output"))
      (node (ref "DA17") (pin "2") (pinfunction "-_2") (pintype "input"))
      (node (ref "R68") (pin "1") (pinfunction "Pin1_1") (pintype "passive"))
    )
    (net (code "60") (name "Net-(DA17B-+)") (class "Default")
      (node (ref "C74") (pin "1") (pintype "passive"))
      (node (ref "DA17") (pin "5") (pinfunction "+_5") (pintype "input"))
      (node (ref "R79") (pin "2") (pinfunction "Pin2_2") (pintype "passive"))
    )
    (net (code "61") (name "Net-(DA17B--)") (class "Default")
      (node (ref "DA17") (pin "6") (pinfunction "-_6") (pintype "input"))
      (node (ref "DA17") (pin "7") (pinfunction "OUT_7") (pintype "output"))
      (node (ref "R93") (pin "1") (pinfunction "Pin1_1") (pintype "passive"))
    )
    (net (code "62") (name "Net-(DA18-CH0FB)") (class "Default")
      (node (ref "DA18") (pin "18") (pinfunction "CH0FB_18") (pintype "output"))
      (node (ref "R99") (pin "1") (pinfunction "Pin1_1") (pintype "passive"))
    )
    (net (code "63") (name "Net-(DA18-CH0IN)") (class "Default")
      (node (ref "DA18") (pin "19") (pinfunction "CH0IN_19") (pintype "output"))
      (node (ref "R100") (pin "1") (pinfunction "Pin1_1") (pintype "passive"))
      (node (ref "R99") (pin "2") (pinfunction "Pin2_2") (pintype "passive"))
    )
    (net (code "64") (name "Net-(DA18-INTOUT)") (class "Default")
      (node (ref "DA18") (pin "4") (pinfunction "INTOUT_4") (pintype "power_in"))
      (node (ref "R84") (pin "2") (pinfunction "Pin2_2") (pintype "passive"))
    )
    (net (code "65") (name "Net-(DA18-INT{slash}~{HOLD})") (class "Default")
      (node (ref "DA18") (pin "7") (pinfunction "INT/~{HOLD}_7") (pintype "output"))
      (node (ref "R85") (pin "1") (pinfunction "Pin1_1") (pintype "passive"))
      (node (ref "VT16") (pin "1") (pinfunction "C_1") (pintype "passive"))
    )
    (net (code "66") (name "Net-(DA18-OSCIN)") (class "Default")
      (node (ref "C77") (pin "1") (pintype "passive"))
      (node (ref "DA18") (pin "9") (pinfunction "OSCIN_9") (pintype "output"))
      (node (ref "R90") (pin "1") (pinfunction "Pin1_1") (pintype "passive"))
      (node (ref "ZQ1") (pin "1") (pinfunction "1_1") (pintype "passive"))
    )
    (net (code "67") (name "Net-(DA18-OSCOUT)") (class "Default")
      (node (ref "C81") (pin "1") (pintype "passive"))
      (node (ref "DA18") (pin "10") (pinfunction "OSCOUT_10") (pintype "output"))
      (node (ref "R90") (pin "2") (pinfunction "Pin2_2") (pintype "passive"))
      (node (ref "ZQ1") (pin "2") (pinfunction "2_2") (pintype "passive"))
    )
    (net (code "68") (name "Net-(DA18-SCK)") (class "Default")
      (node (ref "DA18") (pin "13") (pinfunction "SCK_13") (pintype "output"))
      (node (ref "DD9") (pin "10") (pinfunction "B4_10") (pintype "power_in"))
    )
    (net (code "69") (name "Net-(DA18-SI)") (class "Default")
      (node (ref "DA18") (pin "12") (pinfunction "SI_12") (pintype "output"))
      (node (ref "DD9") (pin "11") (pinfunction "B3_11") (pintype "power_in"))
    )
    (net (code "70") (name "Net-(DA18-SO)") (class "Default")
      (node (ref "DA18") (pin "11") (pinfunction "SO_11") (pintype "output"))
      (node (ref "DD9") (pin "12") (pinfunction "B2_12") (pintype "power_in"))
    )
    (net (code "71") (name "Net-(DA18-~{CS})") (class "Default")
      (node (ref "DA18") (pin "8") (pinfunction "~{CS}_8") (pintype "output"))
      (node (ref "DD9") (pin "13") (pinfunction "B1_13") (pintype "power_in"))
    )
    (net (code "72") (name "Net-(DA19A-+)") (class "Default")
      (node (ref "C78") (pin "1") (pintype "passive"))
      (node (ref "DA19") (pin "3") (pinfunction "+_3") (pintype "input"))
      (node (ref "R88") (pin "2") (pinfunction "Pin2_2") (pintype "passive"))
    )
    (net (code "73") (name "Net-(DA19A--)") (class "Default")
      (node (ref "DA19") (pin "2") (pinfunction "-_2") (pintype "input"))
      (node (ref "R91") (pin "2") (pinfunction "Pin2_2") (pintype "passive"))
      (node (ref "R98") (pin "1") (pinfunction "Pin1_1") (pintype "passive"))
    )
    (net (code "74") (name "Net-(DA19B-+)") (class "Default")
      (node (ref "C79") (pin "1") (pintype "passive"))
      (node (ref "DA19") (pin "5") (pinfunction "+_5") (pintype "input"))
      (node (ref "R89") (pin "2") (pinfunction "Pin2_2") (pintype "passive"))
    )
    (net (code "75") (name "Net-(DA19B--)") (class "Default")
      (node (ref "DA19") (pin "6") (pinfunction "-_6") (pintype "input"))
      (node (ref "R92") (pin "2") (pinfunction "Pin2_2") (pintype "passive"))
      (node (ref "R95") (pin "1") (pinfunction "Pin1_1") (pintype "passive"))
    )
    (net (code "76") (name "Net-(DA25A-+)") (class "Default")
      (node (ref "C128") (pin "1") (pintype "passive"))
      (node (ref "DA25") (pin "3") (pinfunction "+_3") (pintype "input"))
      (node (ref "R164") (pin "2") (pinfunction "Pin2_2") (pintype "passive"))
    )
    (net (code "77") (name "Net-(DA25A--)") (class "Default")
      (node (ref "DA25") (pin "1") (pinfunction "OUT_1") (pintype "output"))
      (node (ref "DA25") (pin "2") (pinfunction "-_2") (pintype "input"))
      (node (ref "R166") (pin "1") (pinfunction "Pin1_1") (pintype "passive"))
    )
    (net (code "78") (name "Net-(DA25B-+)") (class "Default")
      (node (ref "C129") (pin "1") (pintype "passive"))
      (node (ref "DA25") (pin "5") (pinfunction "+_5") (pintype "input"))
      (node (ref "R165") (pin "2") (pinfunction "Pin2_2") (pintype "passive"))
    )
    (net (code "79") (name "Net-(DA25B--)") (class "Default")
      (node (ref "DA25") (pin "6") (pinfunction "-_6") (pintype "input"))
      (node (ref "DA25") (pin "7") (pinfunction "OUT_7") (pintype "output"))
      (node (ref "R167") (pin "1") (pinfunction "Pin1_1") (pintype "passive"))
    )
    (net (code "80") (name "Net-(R78-Pin2)") (class "Default")
      (node (ref "R78") (pin "2") (pinfunction "Pin2_2") (pintype "passive"))
      (node (ref "VT16") (pin "2") (pinfunction "B_2") (pintype "passive"))
    )
    (net (code "81") (name "Net-(R82-Pin1)") (class "Default")
      (node (ref "R82") (pin "1") (pinfunction "Pin1_1") (pintype "passive"))
      (node (ref "R86") (pin "1") (pinfunction "Pin1_1") (pintype "passive"))
      (node (ref "R88") (pin "1") (pinfunction "Pin1_1") (pintype "passive"))
      (node (ref "VT15") (pin "1") (pintype "passive"))
    )
    (net (code "82") (name "Net-(R83-Pin1)") (class "Default")
      (node (ref "R83") (pin "1") (pinfunction "Pin1_1") (pintype "passive"))
      (node (ref "R87") (pin "1") (pinfunction "Pin1_1") (pintype "passive"))
      (node (ref "R89") (pin "1") (pinfunction "Pin1_1") (pintype "passive"))
      (node (ref "VT15") (pin "3") (pintype "passive"))
    )
    (net (code "83") (name "Net-(R100-Pin2)") (class "Default")
      (node (ref "C87") (pin "1") (pintype "passive"))
      (node (ref "R100") (pin "2") (pinfunction "Pin2_2") (pintype "passive"))
    )
    (net (code "84") (name "unconnected-(DA18-CH1FB-Pad17)") (class "Default")
      (node (ref "DA18") (pin "17") (pinfunction "CH1FB_17") (pintype "output"))
    )
    (net (code "85") (name "unconnected-(DA18-CH1IN-Pad16)") (class "Default")
      (node (ref "DA18") (pin "16") (pinfunction "CH1IN_16") (pintype "output"))
    )
    (net (code "86") (name "unconnected-(DA18-CH1NI-Pad15)") (class "Default")
      (node (ref "DA18") (pin "15") (pinfunction "CH1NI_15") (pintype "output"))
    )
    (net (code "87") (name "unconnected-(DA18-~{TEST}-Pad14)") (class "Default")
      (node (ref "DA18") (pin "14") (pinfunction "~{TEST}_14") (pintype "output"))
    )
  )
)
